# l.net
KiCad netlist of a schematic drawn in EAGLE
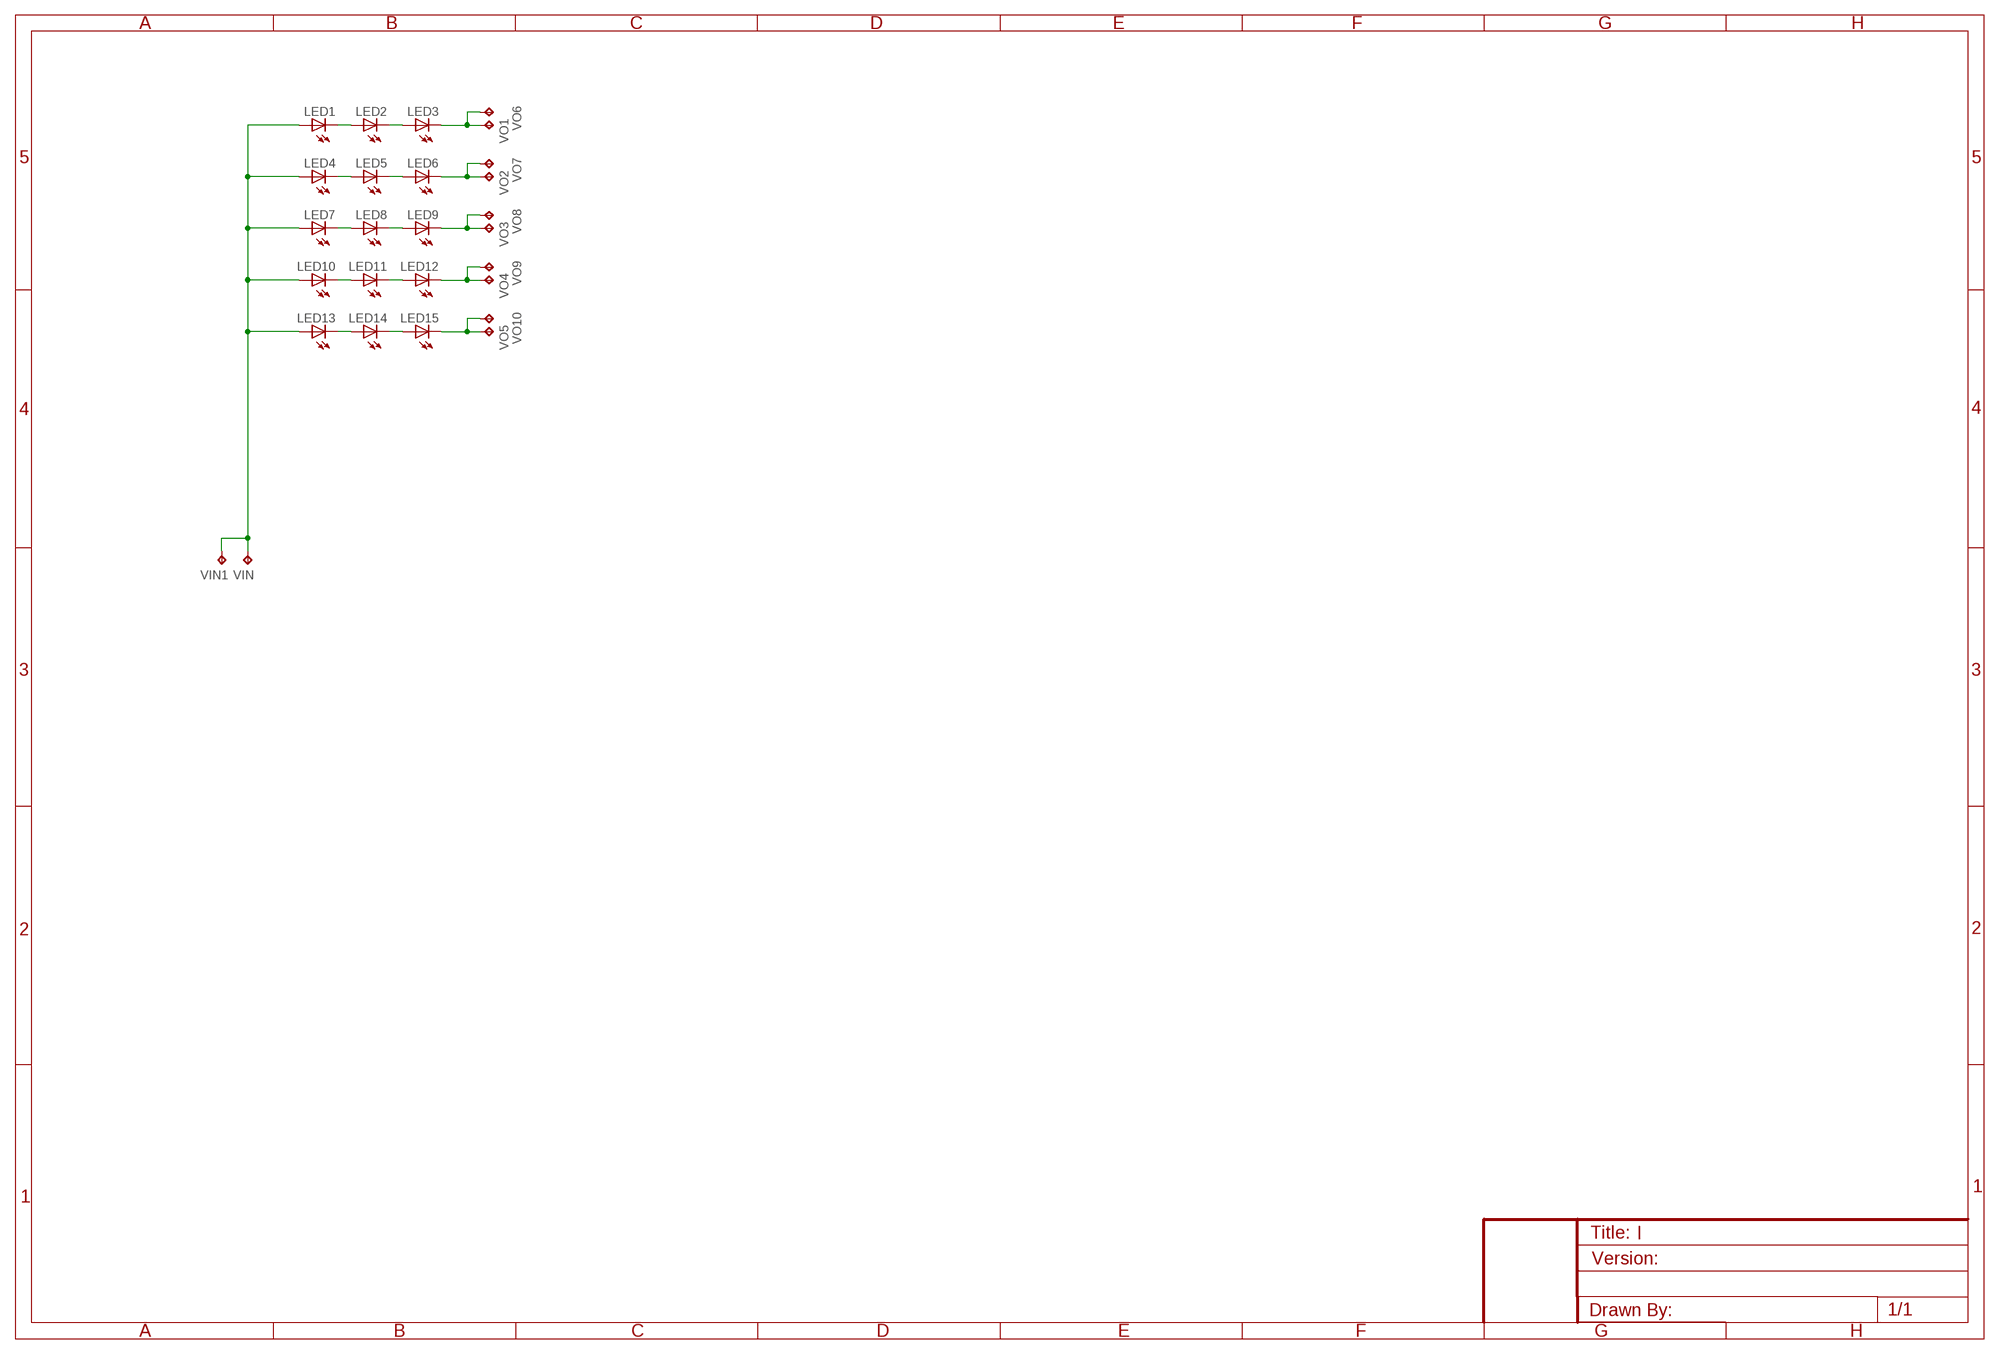
[diagram p0: schematic, sheet 1]

(export (version "E")
  (design (tool "Eeschema 10.0.6"))
  (components
    (comp (ref "LED1")
      (value "LED0805")
      (footprint "eagle-import:LED_0805")
      (libsource (lib "eagle-import") (part "LED0805"))
    )
    (comp (ref "LED2")
      (value "LED0805")
      (footprint "eagle-import:LED_0805")
      (libsource (lib "eagle-import") (part "LED0805"))
    )
    (comp (ref "LED3")
      (value "LED0805")
      (footprint "eagle-import:LED_0805")
      (libsource (lib "eagle-import") (part "LED0805"))
    )
    (comp (ref "LED4")
      (value "LED0805")
      (footprint "eagle-import:LED_0805")
      (libsource (lib "eagle-import") (part "LED0805"))
    )
    (comp (ref "LED5")
      (value "LED0805")
      (footprint "eagle-import:LED_0805")
      (libsource (lib "eagle-import") (part "LED0805"))
    )
    (comp (ref "LED6")
      (value "LED0805")
      (footprint "eagle-import:LED_0805")
      (libsource (lib "eagle-import") (part "LED0805"))
    )
    (comp (ref "LED7")
      (value "LED0805")
      (footprint "eagle-import:LED_0805")
      (libsource (lib "eagle-import") (part "LED0805"))
    )
    (comp (ref "LED8")
      (value "LED0805")
      (footprint "eagle-import:LED_0805")
      (libsource (lib "eagle-import") (part "LED0805"))
    )
    (comp (ref "LED9")
      (value "LED0805")
      (footprint "eagle-import:LED_0805")
      (libsource (lib "eagle-import") (part "LED0805"))
    )
    (comp (ref "LED10")
      (value "LED0805")
      (footprint "eagle-import:LED_0805")
      (libsource (lib "eagle-import") (part "LED0805"))
    )
    (comp (ref "LED11")
      (value "LED0805")
      (footprint "eagle-import:LED_0805")
      (libsource (lib "eagle-import") (part "LED0805"))
    )
    (comp (ref "LED12")
      (value "LED0805")
      (footprint "eagle-import:LED_0805")
      (libsource (lib "eagle-import") (part "LED0805"))
    )
    (comp (ref "LED13")
      (value "LED0805")
      (footprint "eagle-import:LED_0805")
      (libsource (lib "eagle-import") (part "LED0805"))
    )
    (comp (ref "LED14")
      (value "LED0805")
      (footprint "eagle-import:LED_0805")
      (libsource (lib "eagle-import") (part "LED0805"))
    )
    (comp (ref "LED15")
      (value "LED0805")
      (footprint "eagle-import:LED_0805")
      (libsource (lib "eagle-import") (part "LED0805"))
    )
    (comp (ref "VIN")
      (value "TEST_POINTPAD1-20")
      (footprint "eagle-import:P1-20")
      (libsource (lib "eagle-import") (part "TEST_POINTPAD1-20"))
    )
    (comp (ref "VIN1")
      (value "TEST_POINTPAD1-20")
      (footprint "eagle-import:P1-20")
      (libsource (lib "eagle-import") (part "TEST_POINTPAD1-20"))
    )
    (comp (ref "VO1")
      (value "TEST_POINTPAD1-20")
      (footprint "eagle-import:P1-20")
      (libsource (lib "eagle-import") (part "TEST_POINTPAD1-20"))
    )
    (comp (ref "VO2")
      (value "TEST_POINTPAD1-20")
      (footprint "eagle-import:P1-20")
      (libsource (lib "eagle-import") (part "TEST_POINTPAD1-20"))
    )
    (comp (ref "VO3")
      (value "TEST_POINTPAD1-20")
      (footprint "eagle-import:P1-20")
      (libsource (lib "eagle-import") (part "TEST_POINTPAD1-20"))
    )
    (comp (ref "VO4")
      (value "TEST_POINTPAD1-20")
      (footprint "eagle-import:P1-20")
      (libsource (lib "eagle-import") (part "TEST_POINTPAD1-20"))
    )
    (comp (ref "VO5")
      (value "TEST_POINTPAD1-20")
      (footprint "eagle-import:P1-20")
      (libsource (lib "eagle-import") (part "TEST_POINTPAD1-20"))
    )
    (comp (ref "VO6")
      (value "TEST_POINTPAD1-20")
      (footprint "eagle-import:P1-20")
      (libsource (lib "eagle-import") (part "TEST_POINTPAD1-20"))
    )
    (comp (ref "VO7")
      (value "TEST_POINTPAD1-20")
      (footprint "eagle-import:P1-20")
      (libsource (lib "eagle-import") (part "TEST_POINTPAD1-20"))
    )
    (comp (ref "VO8")
      (value "TEST_POINTPAD1-20")
      (footprint "eagle-import:P1-20")
      (libsource (lib "eagle-import") (part "TEST_POINTPAD1-20"))
    )
    (comp (ref "VO9")
      (value "TEST_POINTPAD1-20")
      (footprint "eagle-import:P1-20")
      (libsource (lib "eagle-import") (part "TEST_POINTPAD1-20"))
    )
    (comp (ref "VO10")
      (value "TEST_POINTPAD1-20")
      (footprint "eagle-import:P1-20")
      (libsource (lib "eagle-import") (part "TEST_POINTPAD1-20"))
    )
  )
  (nets
    (net (code "1") (name "Net-(LED1-PadA)") (class "Default")
      (node (ref "LED1") (pin "A") (pinfunction "A_A") (pintype "passive"))
      (node (ref "LED10") (pin "A") (pinfunction "A_A") (pintype "passive"))
      (node (ref "LED13") (pin "A") (pinfunction "A_A") (pintype "passive"))
      (node (ref "LED4") (pin "A") (pinfunction "A_A") (pintype "passive"))
      (node (ref "LED7") (pin "A") (pinfunction "A_A") (pintype "passive"))
      (node (ref "VIN") (pin "TP") (pinfunction "TP_TP") (pintype "input"))
      (node (ref "VIN1") (pin "TP") (pinfunction "TP_TP") (pintype "input"))
    )
    (net (code "2") (name "Net-(LED1-PadC)") (class "Default")
      (node (ref "LED1") (pin "C") (pinfunction "C_C") (pintype "passive"))
      (node (ref "LED2") (pin "A") (pinfunction "A_A") (pintype "passive"))
    )
    (net (code "3") (name "Net-(LED2-PadC)") (class "Default")
      (node (ref "LED2") (pin "C") (pinfunction "C_C") (pintype "passive"))
      (node (ref "LED3") (pin "A") (pinfunction "A_A") (pintype "passive"))
    )
    (net (code "4") (name "Net-(LED3-PadC)") (class "Default")
      (node (ref "LED3") (pin "C") (pinfunction "C_C") (pintype "passive"))
      (node (ref "VO1") (pin "TP") (pinfunction "TP_TP") (pintype "input"))
      (node (ref "VO6") (pin "TP") (pinfunction "TP_TP") (pintype "input"))
    )
    (net (code "5") (name "Net-(LED4-PadC)") (class "Default")
      (node (ref "LED4") (pin "C") (pinfunction "C_C") (pintype "passive"))
      (node (ref "LED5") (pin "A") (pinfunction "A_A") (pintype "passive"))
    )
    (net (code "6") (name "Net-(LED5-PadC)") (class "Default")
      (node (ref "LED5") (pin "C") (pinfunction "C_C") (pintype "passive"))
      (node (ref "LED6") (pin "A") (pinfunction "A_A") (pintype "passive"))
    )
    (net (code "7") (name "Net-(LED6-PadC)") (class "Default")
      (node (ref "LED6") (pin "C") (pinfunction "C_C") (pintype "passive"))
      (node (ref "VO2") (pin "TP") (pinfunction "TP_TP") (pintype "input"))
      (node (ref "VO7") (pin "TP") (pinfunction "TP_TP") (pintype "input"))
    )
    (net (code "8") (name "Net-(LED7-PadC)") (class "Default")
      (node (ref "LED7") (pin "C") (pinfunction "C_C") (pintype "passive"))
      (node (ref "LED8") (pin "A") (pinfunction "A_A") (pintype "passive"))
    )
    (net (code "9") (name "Net-(LED8-PadC)") (class "Default")
      (node (ref "LED8") (pin "C") (pinfunction "C_C") (pintype "passive"))
      (node (ref "LED9") (pin "A") (pinfunction "A_A") (pintype "passive"))
    )
    (net (code "10") (name "Net-(LED9-PadC)") (class "Default")
      (node (ref "LED9") (pin "C") (pinfunction "C_C") (pintype "passive"))
      (node (ref "VO3") (pin "TP") (pinfunction "TP_TP") (pintype "input"))
      (node (ref "VO8") (pin "TP") (pinfunction "TP_TP") (pintype "input"))
    )
    (net (code "11") (name "Net-(LED10-PadC)") (class "Default")
      (node (ref "LED10") (pin "C") (pinfunction "C_C") (pintype "passive"))
      (node (ref "LED11") (pin "A") (pinfunction "A_A") (pintype "passive"))
    )
    (net (code "12") (name "Net-(LED11-PadC)") (class "Default")
      (node (ref "LED11") (pin "C") (pinfunction "C_C") (pintype "passive"))
      (node (ref "LED12") (pin "A") (pinfunction "A_A") (pintype "passive"))
    )
    (net (code "13") (name "Net-(LED12-PadC)") (class "Default")
      (node (ref "LED12") (pin "C") (pinfunction "C_C") (pintype "passive"))
      (node (ref "VO4") (pin "TP") (pinfunction "TP_TP") (pintype "input"))
      (node (ref "VO9") (pin "TP") (pinfunction "TP_TP") (pintype "input"))
    )
    (net (code "14") (name "Net-(LED13-PadC)") (class "Default")
      (node (ref "LED13") (pin "C") (pinfunction "C_C") (pintype "passive"))
      (node (ref "LED14") (pin "A") (pinfunction "A_A") (pintype "passive"))
    )
    (net (code "15") (name "Net-(LED14-PadC)") (class "Default")
      (node (ref "LED14") (pin "C") (pinfunction "C_C") (pintype "passive"))
      (node (ref "LED15") (pin "A") (pinfunction "A_A") (pintype "passive"))
    )
    (net (code "16") (name "Net-(LED15-PadC)") (class "Default")
      (node (ref "LED15") (pin "C") (pinfunction "C_C") (pintype "passive"))
      (node (ref "VO10") (pin "TP") (pinfunction "TP_TP") (pintype "input"))
      (node (ref "VO5") (pin "TP") (pinfunction "TP_TP") (pintype "input"))
    )
  )
)
